# breakout_SX1278_green.net
KiCad netlist of a schematic drawn in EAGLE
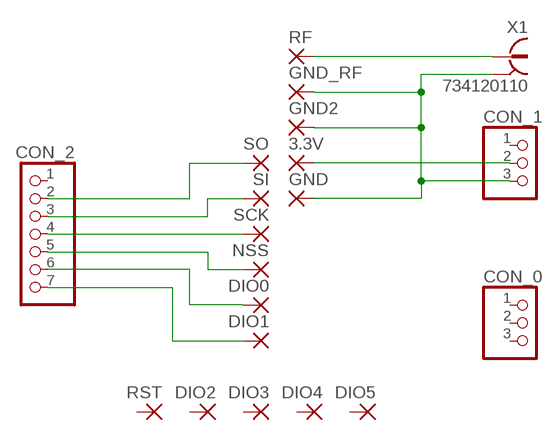
[diagram p0: schematic, sheet 1]

(export (version "E")
  (design (tool "Eeschema 10.0.6"))
  (components
    (comp (ref "3.3V")
      (value "SMD2")
      (footprint "eagle-import:SMD1,27-2,54")
      (libsource (lib "eagle-import") (part "SMD2"))
    )
    (comp (ref "CON_0")
      (value "PINHD-1X3")
      (footprint "eagle-import:1X03")
      (libsource (lib "eagle-import") (part "PINHD-1X3"))
    )
    (comp (ref "CON_1")
      (value "PINHD-1X3")
      (footprint "eagle-import:1X03")
      (libsource (lib "eagle-import") (part "PINHD-1X3"))
    )
    (comp (ref "CON_2")
      (value "PINHD-1X7")
      (footprint "eagle-import:1X07")
      (libsource (lib "eagle-import") (part "PINHD-1X7"))
    )
    (comp (ref "DIO0")
      (value "SMD2")
      (footprint "eagle-import:SMD1,27-2,54")
      (libsource (lib "eagle-import") (part "SMD2"))
    )
    (comp (ref "DIO1")
      (value "SMD2")
      (footprint "eagle-import:SMD1,27-2,54")
      (libsource (lib "eagle-import") (part "SMD2"))
    )
    (comp (ref "DIO2")
      (value "SMD2")
      (footprint "eagle-import:SMD1,27-2,54")
      (libsource (lib "eagle-import") (part "SMD2"))
    )
    (comp (ref "DIO3")
      (value "SMD2")
      (footprint "eagle-import:SMD1,27-2,54")
      (libsource (lib "eagle-import") (part "SMD2"))
    )
    (comp (ref "DIO4")
      (value "SMD2")
      (footprint "eagle-import:SMD1,27-2,54")
      (libsource (lib "eagle-import") (part "SMD2"))
    )
    (comp (ref "DIO5")
      (value "SMD2")
      (footprint "eagle-import:SMD1,27-2,54")
      (libsource (lib "eagle-import") (part "SMD2"))
    )
    (comp (ref "GND")
      (value "SMD2")
      (footprint "eagle-import:SMD1,27-2,54")
      (libsource (lib "eagle-import") (part "SMD2"))
    )
    (comp (ref "GND2")
      (value "SMD2")
      (footprint "eagle-import:SMD1,27-2,54")
      (libsource (lib "eagle-import") (part "SMD2"))
    )
    (comp (ref "GND_RF")
      (value "SMD2")
      (footprint "eagle-import:SMD1,27-2,54")
      (libsource (lib "eagle-import") (part "SMD2"))
    )
    (comp (ref "NSS")
      (value "SMD2")
      (footprint "eagle-import:SMD1,27-2,54")
      (libsource (lib "eagle-import") (part "SMD2"))
    )
    (comp (ref "RF")
      (value "SMD2")
      (footprint "eagle-import:SMD1,27-2,54")
      (libsource (lib "eagle-import") (part "SMD2"))
    )
    (comp (ref "RST")
      (value "SMD2")
      (footprint "eagle-import:SMD1,27-2,54")
      (libsource (lib "eagle-import") (part "SMD2"))
    )
    (comp (ref "SCK")
      (value "SMD2")
      (footprint "eagle-import:SMD1,27-2,54")
      (libsource (lib "eagle-import") (part "SMD2"))
    )
    (comp (ref "SI")
      (value "SMD2")
      (footprint "eagle-import:SMD1,27-2,54")
      (libsource (lib "eagle-import") (part "SMD2"))
    )
    (comp (ref "SO")
      (value "SMD2")
      (footprint "eagle-import:SMD1,27-2,54")
      (libsource (lib "eagle-import") (part "SMD2"))
    )
    (comp (ref "X1")
      (value "734120110")
      (footprint "eagle-import:734120110")
      (libsource (lib "eagle-import") (part "734120110"))
    )
  )
  (nets
    (net (code "1") (name "Net-(3.3V-P)") (class "Default")
      (node (ref "3.3V") (pin "1") (pinfunction "P_1") (pintype "passive"))
      (node (ref "CON_1") (pin "2") (pinfunction "2_2") (pintype "passive"))
    )
    (net (code "2") (name "Net-(DIO0-P)") (class "Default")
      (node (ref "CON_2") (pin "6") (pinfunction "6_6") (pintype "passive"))
      (node (ref "DIO0") (pin "1") (pinfunction "P_1") (pintype "passive"))
    )
    (net (code "3") (name "Net-(DIO1-P)") (class "Default")
      (node (ref "CON_2") (pin "7") (pinfunction "7_7") (pintype "passive"))
      (node (ref "DIO1") (pin "1") (pinfunction "P_1") (pintype "passive"))
    )
    (net (code "4") (name "Net-(GND-P)") (class "Default")
      (node (ref "CON_1") (pin "3") (pinfunction "3_3") (pintype "passive"))
      (node (ref "GND") (pin "1") (pinfunction "P_1") (pintype "passive"))
      (node (ref "GND2") (pin "1") (pinfunction "P_1") (pintype "passive"))
      (node (ref "GND_RF") (pin "1") (pinfunction "P_1") (pintype "passive"))
      (node (ref "X1") (pin "S@1") (pinfunction "2_S@1") (pintype "passive"))
      (node (ref "X1") (pin "S@2") (pinfunction "2_S@2") (pintype "passive"))
      (node (ref "X1") (pin "S@3") (pinfunction "2_S@3") (pintype "passive"))
    )
    (net (code "5") (name "Net-(NSS-P)") (class "Default")
      (node (ref "CON_2") (pin "5") (pinfunction "5_5") (pintype "passive"))
      (node (ref "NSS") (pin "1") (pinfunction "P_1") (pintype "passive"))
    )
    (net (code "6") (name "Net-(RF-P)") (class "Default")
      (node (ref "RF") (pin "1") (pinfunction "P_1") (pintype "passive"))
      (node (ref "X1") (pin "1") (pinfunction "1_1") (pintype "passive"))
    )
    (net (code "7") (name "Net-(SCK-P)") (class "Default")
      (node (ref "CON_2") (pin "4") (pinfunction "4_4") (pintype "passive"))
      (node (ref "SCK") (pin "1") (pinfunction "P_1") (pintype "passive"))
    )
    (net (code "8") (name "Net-(SI-P)") (class "Default")
      (node (ref "CON_2") (pin "3") (pinfunction "3_3") (pintype "passive"))
      (node (ref "SI") (pin "1") (pinfunction "P_1") (pintype "passive"))
    )
    (net (code "9") (name "Net-(SO-P)") (class "Default")
      (node (ref "CON_2") (pin "2") (pinfunction "2_2") (pintype "passive"))
      (node (ref "SO") (pin "1") (pinfunction "P_1") (pintype "passive"))
    )
    (net (code "10") (name "unconnected-(CON_0-Pad1)") (class "Default")
      (node (ref "CON_0") (pin "1") (pinfunction "1_1") (pintype "passive"))
    )
    (net (code "11") (name "unconnected-(CON_0-Pad2)") (class "Default")
      (node (ref "CON_0") (pin "2") (pinfunction "2_2") (pintype "passive"))
    )
    (net (code "12") (name "unconnected-(CON_0-Pad3)") (class "Default")
      (node (ref "CON_0") (pin "3") (pinfunction "3_3") (pintype "passive"))
    )
    (net (code "13") (name "unconnected-(CON_1-Pad1)") (class "Default")
      (node (ref "CON_1") (pin "1") (pinfunction "1_1") (pintype "passive"))
    )
    (net (code "14") (name "unconnected-(CON_2-Pad1)") (class "Default")
      (node (ref "CON_2") (pin "1") (pinfunction "1_1") (pintype "passive"))
    )
    (net (code "15") (name "unconnected-(DIO2-P-Pad1)") (class "Default")
      (node (ref "DIO2") (pin "1") (pinfunction "P_1") (pintype "passive"))
    )
    (net (code "16") (name "unconnected-(DIO3-P-Pad1)") (class "Default")
      (node (ref "DIO3") (pin "1") (pinfunction "P_1") (pintype "passive"))
    )
    (net (code "17") (name "unconnected-(DIO4-P-Pad1)") (class "Default")
      (node (ref "DIO4") (pin "1") (pinfunction "P_1") (pintype "passive"))
    )
    (net (code "18") (name "unconnected-(DIO5-P-Pad1)") (class "Default")
      (node (ref "DIO5") (pin "1") (pinfunction "P_1") (pintype "passive"))
    )
    (net (code "19") (name "unconnected-(RST-P-Pad1)") (class "Default")
      (node (ref "RST") (pin "1") (pinfunction "P_1") (pintype "passive"))
    )
  )
)
